# H1DR1x-T.net
KiCad netlist of a schematic drawn in EAGLE
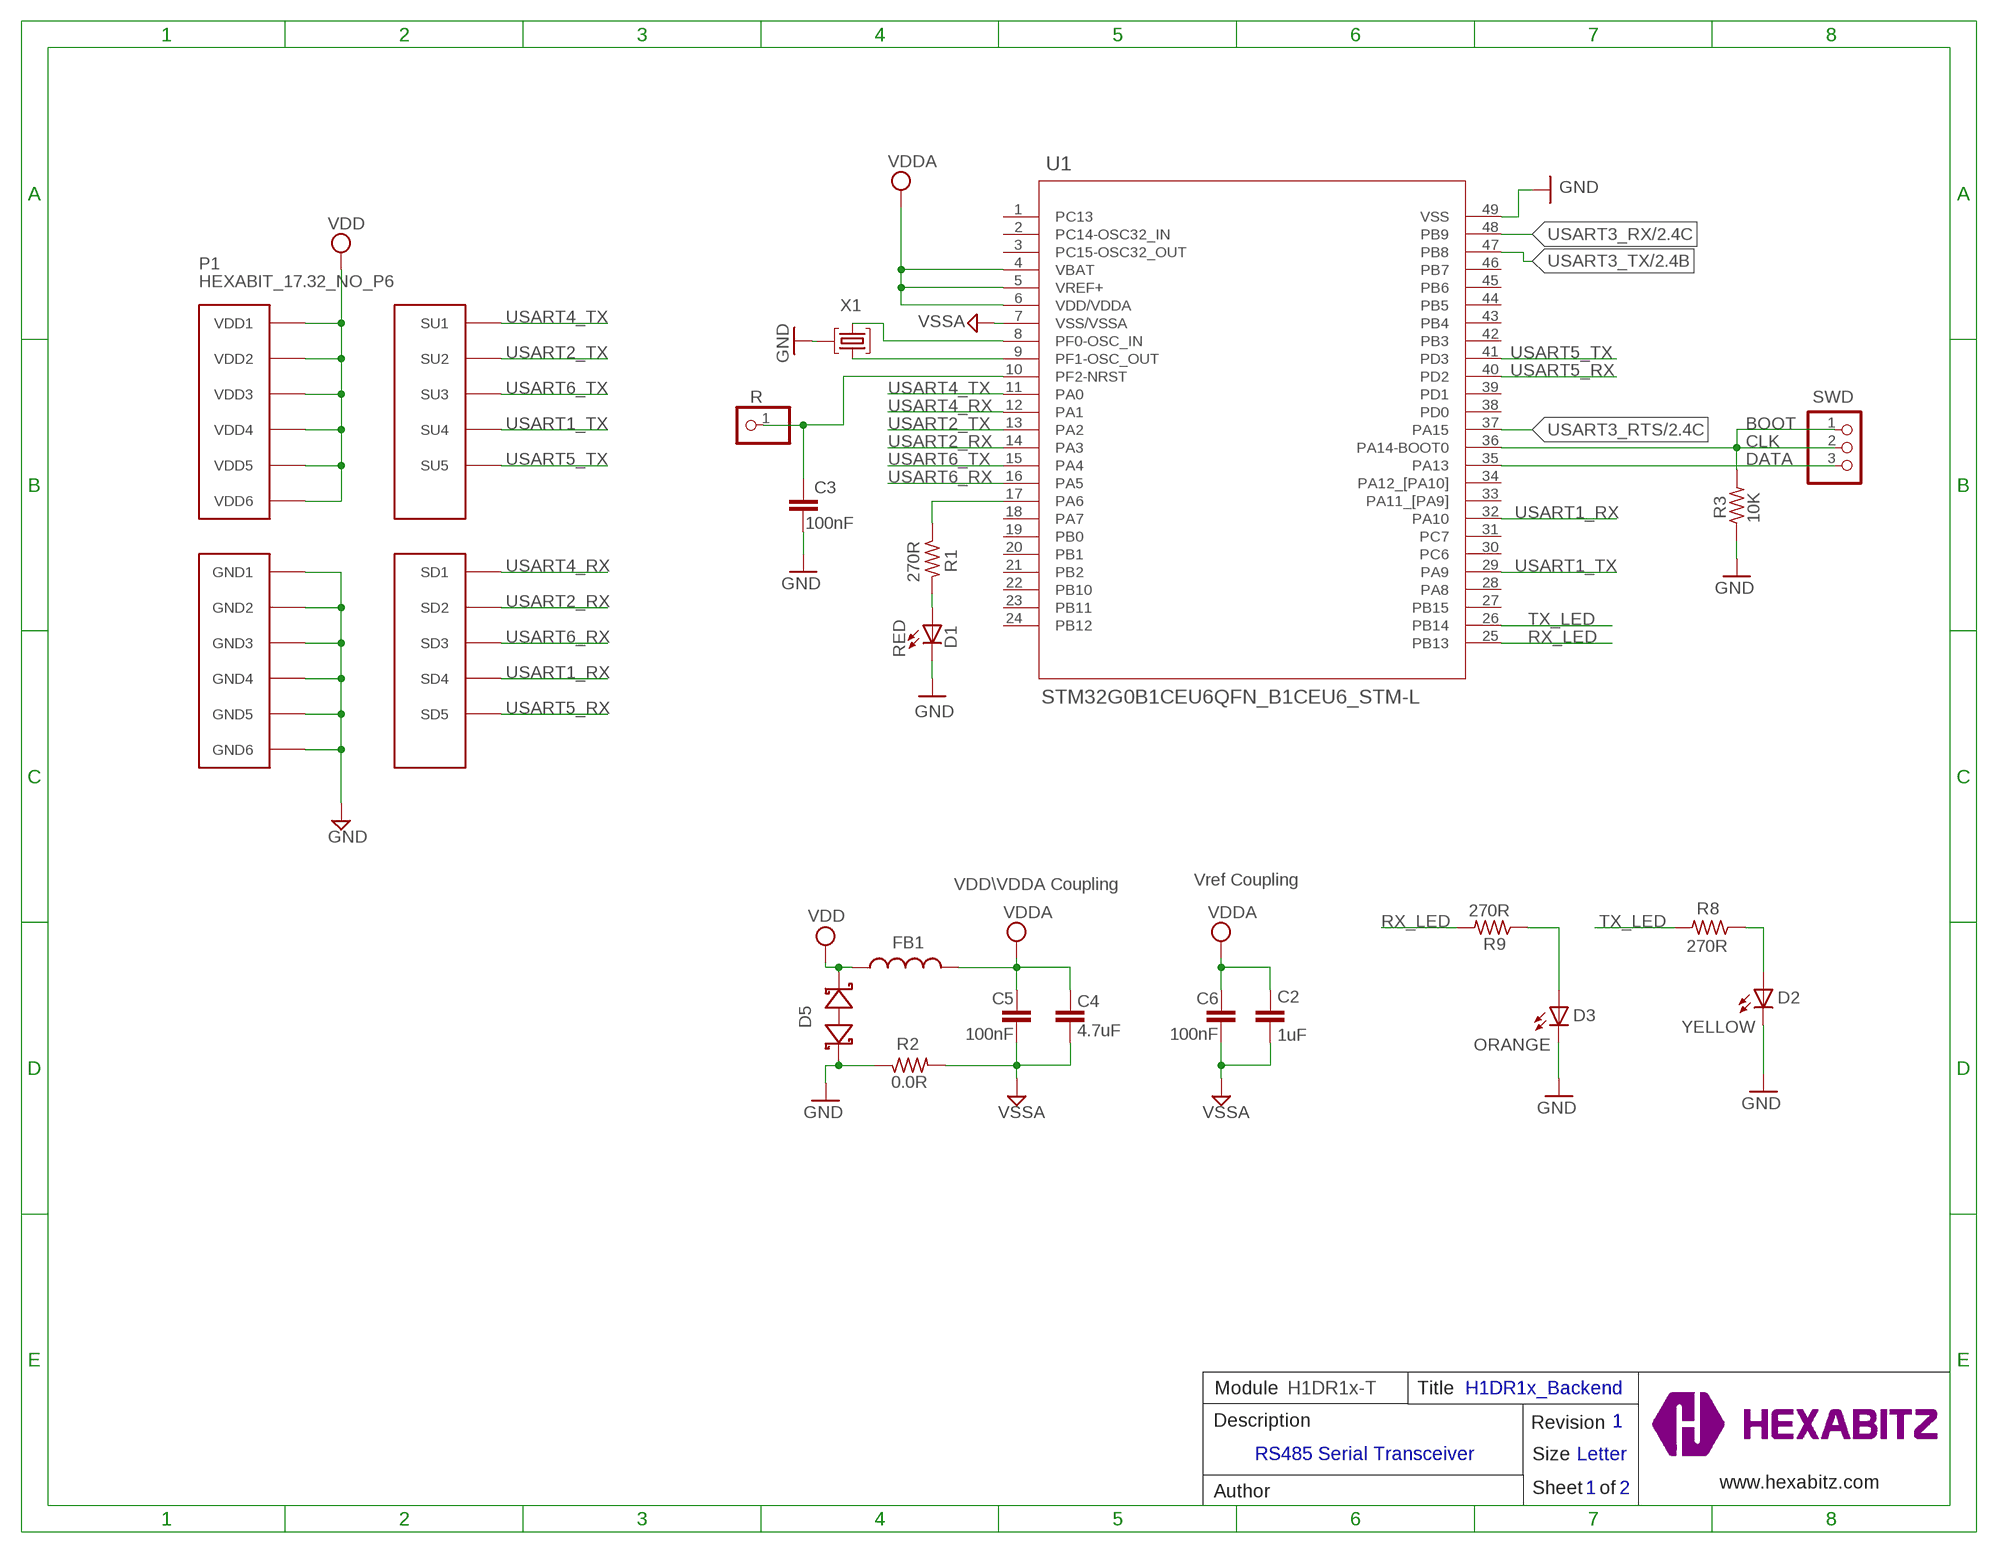
[diagram p0: schematic, sheet 1]
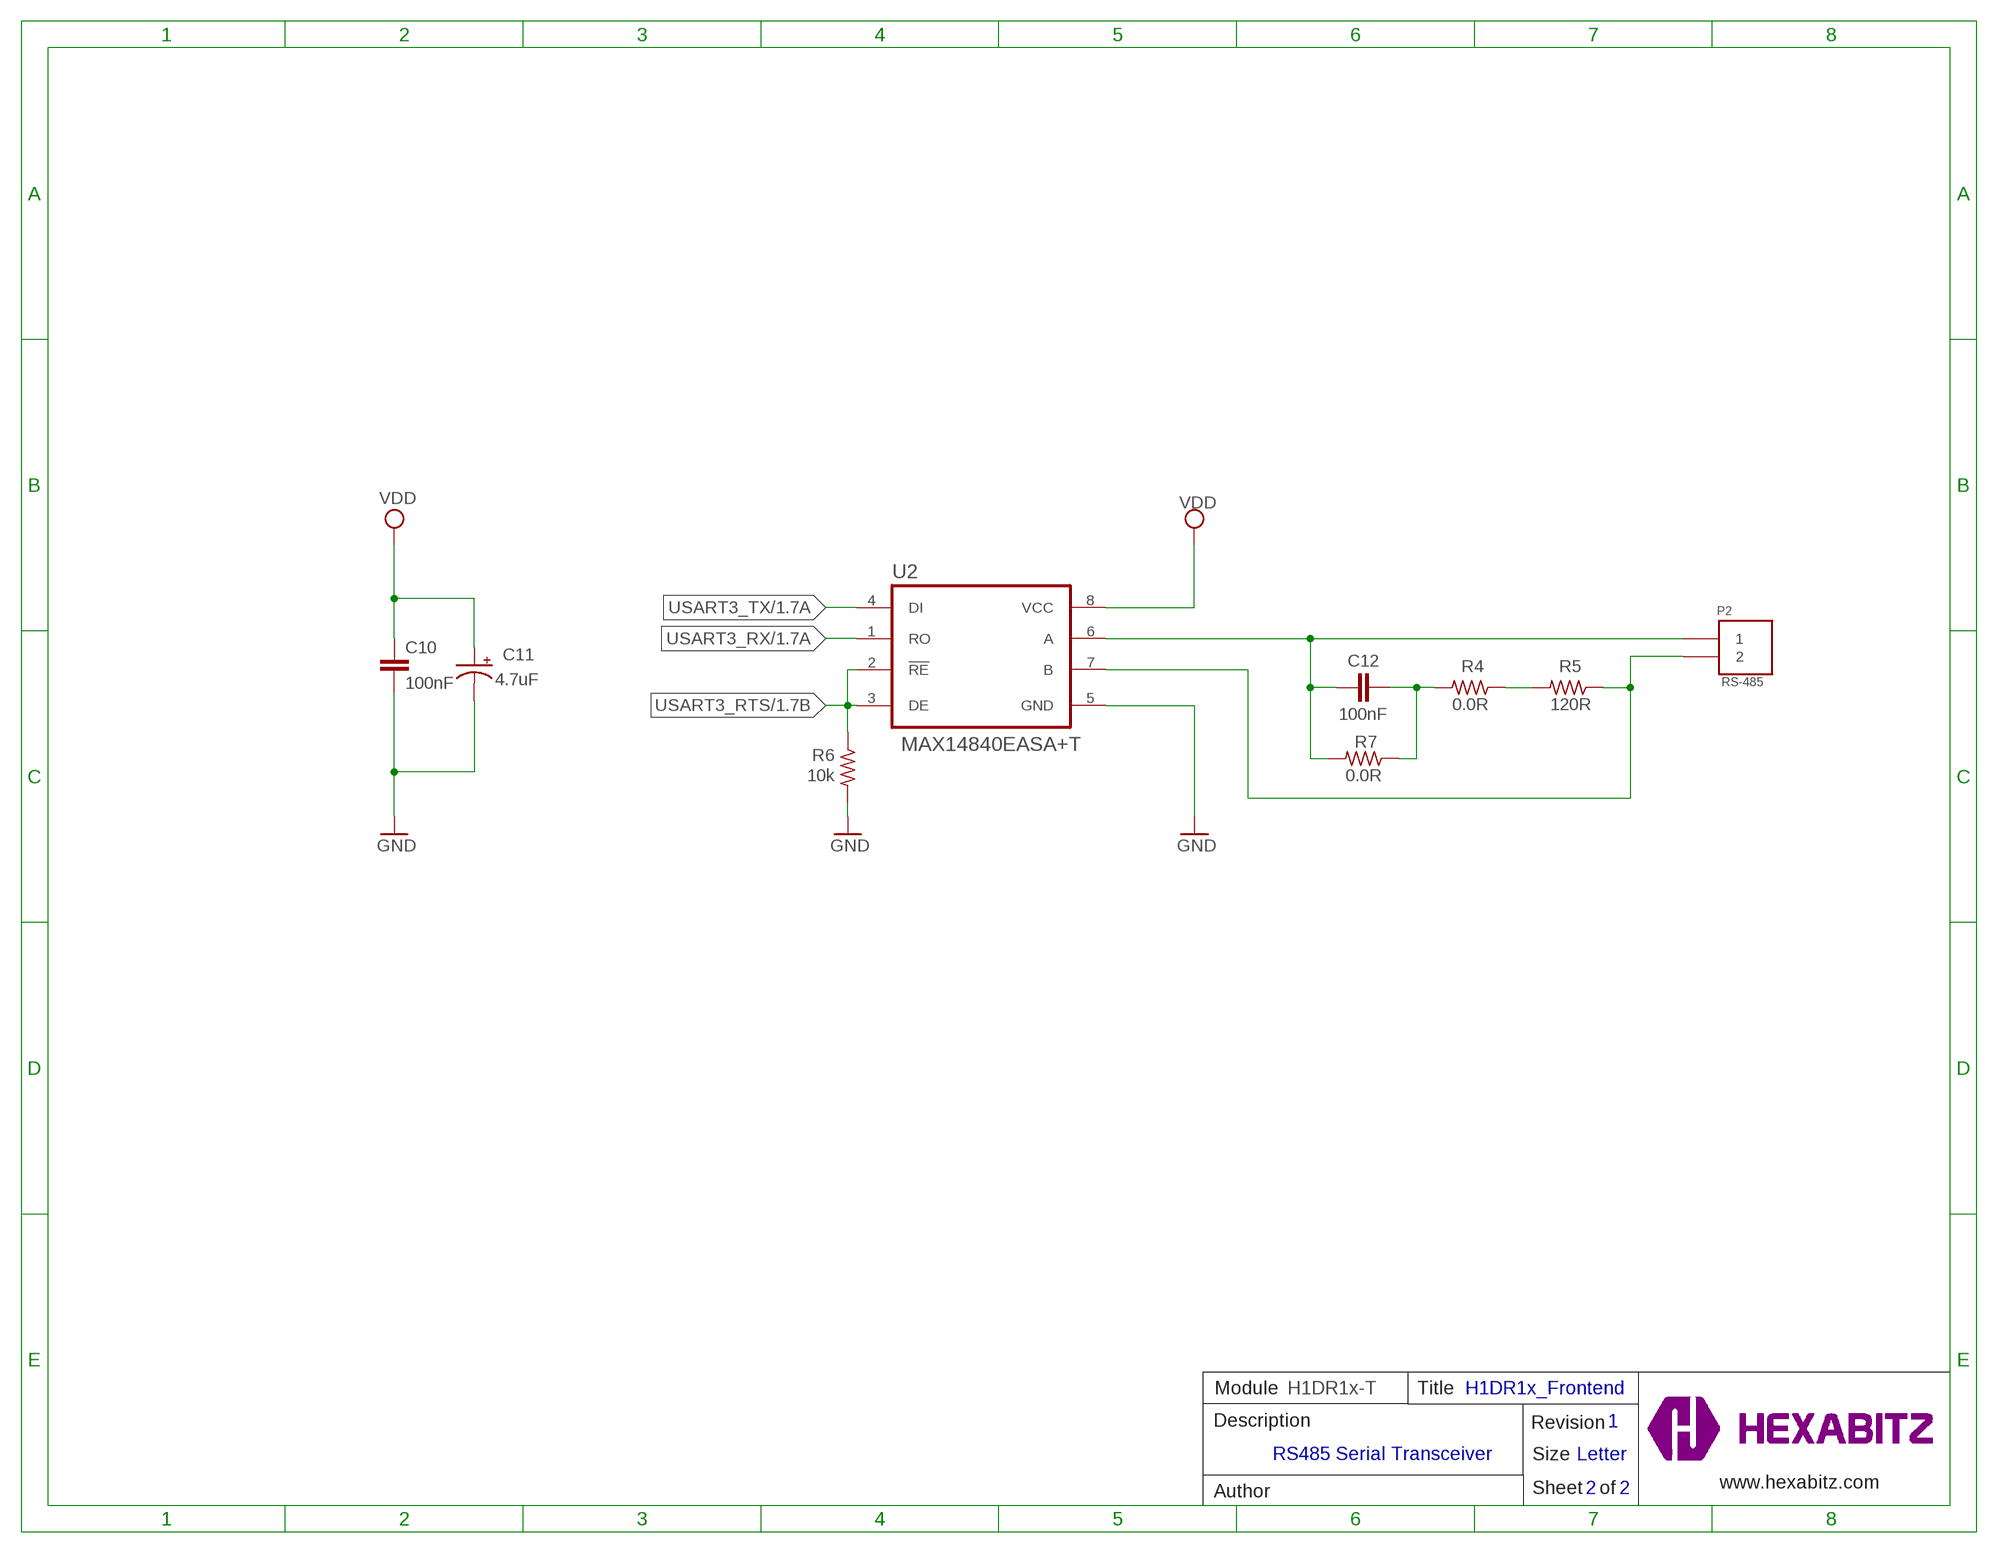
[diagram p1: schematic, sheet 2]

(export (version "E")
  (design (tool "Eeschema 10.0.6"))
  (components
    (comp (ref "C2")
      (value "1uF")
      (footprint "eagle-import:C-0805")
      (libsource (lib "eagle-import") (part "C-0805"))
    )
    (comp (ref "C3")
      (value "100nF")
      (footprint "eagle-import:C-0603")
      (libsource (lib "eagle-import") (part "C-0603"))
    )
    (comp (ref "C4")
      (value "4.7uF")
      (footprint "eagle-import:C-0805")
      (libsource (lib "eagle-import") (part "C-0805"))
    )
    (comp (ref "C5")
      (value "100nF")
      (footprint "eagle-import:C-0603")
      (libsource (lib "eagle-import") (part "C-0603"))
    )
    (comp (ref "C6")
      (value "100nF")
      (footprint "eagle-import:C-0603")
      (libsource (lib "eagle-import") (part "C-0603"))
    )
    (comp (ref "D1")
      (value "RED")
      (footprint "eagle-import:VLMS1300-GS08")
      (fields
        (field (name "MPN") "VLMS1300-GS08")
        (field (name "MFN") "Vishay")
        (field (name "MPN_1") "VLMS1300-GS08")
        (field (name "OCTOPART_URL") "https://octopart.com/vlms1300-gs08-vishay-21709201?r=sp&s=_gcP4_q8T1SC6PJQPTQ9yA")
      )
      (libsource (lib "eagle-import") (part "VLMS1300-GS08"))
    )
    (comp (ref "D2")
      (value "YELLOW")
      (footprint "eagle-import:VLMS1300-GS08")
      (fields
        (field (name "MPN") "VLMS1300-GS08")
        (field (name "OCTOPART_URL") "https://octopart.com/vlms1300-gs08-vishay-21709201?r=sp&s=_gcP4_q8T1SC6PJQPTQ9yA")
      )
      (libsource (lib "eagle-import") (part "VLMS1300-GS08"))
    )
    (comp (ref "D3")
      (value "ORANGE")
      (footprint "eagle-import:VLMS1300-GS08")
      (fields
        (field (name "MPN") "VLMS1300-GS08")
        (field (name "OCTOPART_URL") "https://octopart.com/vlms1300-gs08-vishay-21709201?r=sp&s=_gcP4_q8T1SC6PJQPTQ9yA")
      )
      (libsource (lib "eagle-import") (part "VLMS1300-GS08"))
    )
    (comp (ref "D5")
      (value "BOURNS_CDSOD323-T03SCBOURNS_CDSOD323-T03SC_0_0")
      (footprint "eagle-import:BOURNS_CDSOD323-T03SC_0")
      (fields (field (name "MPN") "CDSOD323-T03SC"))
      (libsource (lib "eagle-import") (part "BOURNS_CDSOD323-T03SCBOURNS_CDSOD323-T03SC_0_0"))
    )
    (comp (ref "FB1")
      (value "FB-TDK_MMZ1608Y300B")
      (footprint "eagle-import:FB-0603")
      (fields
        (field (name "MFN") "TDK ")
        (field (name "MPN") "MMZ1608Y300B")
        (field (name "OCTOPART_URL") "https://octopart.com/mmz1608y300b-tdk-368280?r=sp&s=cd9_2ZEqQ9q9UNBuQgHAiA")
      )
      (libsource (lib "eagle-import") (part "FB-0603"))
    )
    (comp (ref "P1")
      (value "HEXABIT_17.32_NO_P6")
      (footprint "eagle-import:HEXABIT_17.32_NO_P6")
      (libsource (lib "eagle-import") (part "HEXABIT_?_NO_P617.32"))
    )
    (comp (ref "R")
      (value "R")
      (footprint "eagle-import:1X01")
      (fields (field (name "MPN") "87227-1"))
      (libsource (lib "eagle-import") (part "PINHD-1X1"))
    )
    (comp (ref "R1")
      (value "270R")
      (footprint "eagle-import:R-0603")
      (libsource (lib "eagle-import") (part "R-0603"))
    )
    (comp (ref "R2")
      (value "0.0R")
      (footprint "eagle-import:R-0603")
      (fields
        (field (name "MFN") "Yageo")
        (field (name "MPN") "RC0603JR-070RL")
        (field (name "OCTOPART_URL") "https://octopart.com/rc0603jr-070rl-yageo-1241539?r=sp&s=X2NteqRjRNWrnx42Y0aliA")
        (field (name "RESISTANCE") "0.0 Ohm")
      )
      (libsource (lib "eagle-import") (part "R-0603"))
    )
    (comp (ref "R3")
      (value "10K")
      (footprint "eagle-import:R-0603")
      (libsource (lib "eagle-import") (part "R-0603"))
    )
    (comp (ref "R8")
      (value "270R")
      (footprint "eagle-import:R-0603")
      (libsource (lib "eagle-import") (part "R-0603"))
    )
    (comp (ref "R9")
      (value "270R")
      (footprint "eagle-import:R-0603")
      (libsource (lib "eagle-import") (part "R-0603"))
    )
    (comp (ref "SWD")
      (value "PINHD-1X3")
      (footprint "eagle-import:1X03")
      (libsource (lib "eagle-import") (part "PINHD-1X3"))
    )
    (comp (ref "TRIMBLE-LOGO1")
      (value "HEXA-LOGO")
      (footprint "eagle-import:HEXA-LOGO")
      (libsource (lib "eagle-import") (part "HEXA-LOGO"))
    )
    (comp (ref "U1")
      (value "STM32G0B1CEU6QFN_B1CEU6_STM-L")
      (footprint "eagle-import:QFN_B1CEU6_STM-L")
      (fields
        (field (name "MANUFACTURER_PART_NUMBER") "STM32G0B1CEU6")
        (field (name "SPICEPREFIX") "X")
        (field (name "COPYRIGHT") "Copyright (C) 2021 Ultra Librarian. All rights reserved.")
      )
      (libsource (lib "eagle-import") (part "STM32G0B1CEU6QFN_B1CEU6_STM-L"))
    )
    (comp (ref "X1")
      (value "XTALL_CSTCE8M00G52")
      (footprint "eagle-import:XTALL_CSTCE8M00G52")
      (fields (field (name "MPN") "CSTCE8M00G52Z-R0"))
      (libsource (lib "eagle-import") (part "XTALL_CSTCE8M00G52"))
    )
    (comp (ref "C10")
      (value "100nF")
      (footprint "eagle-import:C-0603")
      (fields
        (field (name "CAPACITANCE") "100nF")
        (field (name "MFN") "KEMET")
        (field (name "MPN") "C0603C104K8RACTU")
        (field (name "OCTOPART_URL") "https://octopart.com/c0603c104k8ractu-kemet-145075?r=sp&s=9bS9ASSwSEqMCE9KBEQZ0g")
        (field (name "TOLERANCE") "10%")
        (field (name "VOLTAGE_RATING") "10V")
      )
      (libsource (lib "eagle-import") (part "C-0603"))
    )
    (comp (ref "C11")
      (value "4.7uF")
      (footprint "eagle-import:C-0805-POL")
      (fields
        (field (name "CAPACITANCE") "4.7uF")
        (field (name "MFN") "Murata")
        (field (name "MPN") "GRM21BC81E475KA12L")
        (field (name "OCTOPART_URL") "https://octopart.com/grm21bc81e475ka12l-murata-10331911?r=sp&s=RY3qZSD8T6mG6TC9CHI5qQ")
        (field (name "TOLERANCE") "10%")
        (field (name "VOLTAGE_RATING") "25V")
      )
      (libsource (lib "eagle-import") (part "C-0805-POL"))
    )
    (comp (ref "C12")
      (value "100nF")
      (footprint "eagle-import:C-0603")
      (fields
        (field (name "CAPACITANCE") "100nF")
        (field (name "MFN") "AVX")
        (field (name "MPN") "0603YC104K4T2A")
        (field (name "OCTOPART_URL") "https://octopart.com/0603yc104k4t2a-avx+interconnect+%2F+elco-8120651")
        (field (name "TOLERANCE") "10%")
        (field (name "VOLTAGE_RATING") "16V")
      )
      (libsource (lib "eagle-import") (part "C-0603"))
    )
    (comp (ref "P2")
      (value "RS-485")
      (footprint "eagle-import:1546111-2")
      (fields (field (name "MPN") "1546111-2"))
      (libsource (lib "eagle-import") (part "1546111-2"))
    )
    (comp (ref "R4")
      (value "0.0R")
      (footprint "eagle-import:R-0603")
      (fields
        (field (name "MFN") "Vishay")
        (field (name "MPN") "CRCW06030000Z0EA")
        (field (name "OCTOPART_URL") "https://octopart.com/crcw06030000z0ea-vishay-39556096#")
        (field (name "RESISTANCE") "0.0 Ohm")
      )
      (libsource (lib "eagle-import") (part "R-0603"))
    )
    (comp (ref "R5")
      (value "120R")
      (footprint "eagle-import:R-0603")
      (fields
        (field (name "MFN") "Panasonic")
        (field (name "MPN") "ERJP6WF1200V")
        (field (name "OCTOPART_URL") "https://octopart.com/erjp6wf1200v-panasonic-25949195?r=sp#")
        (field (name "RESISTANCE") "120R")
        (field (name "TOLERANCE") "1%")
      )
      (libsource (lib "eagle-import") (part "R-0603"))
    )
    (comp (ref "R6")
      (value "10k")
      (footprint "eagle-import:R-0603")
      (fields
        (field (name "MFN") "Vishay")
        (field (name "MPN") "CRCW060310K0JNEB")
        (field (name "OCTOPART_URL") "https://octopart.com/crcw060310k0jneb-vishay+dale-46603268")
        (field (name "RESISTANCE") "10k")
        (field (name "TOLERANCE") "5%")
      )
      (libsource (lib "eagle-import") (part "R-0603"))
    )
    (comp (ref "R7")
      (value "0.0R")
      (footprint "eagle-import:R-0603")
      (fields
        (field (name "MFN") "Vishay")
        (field (name "MPN") "CRCW06030000Z0EA")
        (field (name "OCTOPART_URL") "https://octopart.com/crcw06030000z0ea-vishay-39556096#")
        (field (name "RESISTANCE") "0.0 Ohm")
      )
      (libsource (lib "eagle-import") (part "R-0603"))
    )
    (comp (ref "U2")
      (value "MAX14840EASA+T")
      (footprint "eagle-import:SOIC127P600X175-8N")
      (fields (field (name "MF") "Analog Devices"))
      (libsource (lib "eagle-import") (part "MAX14840EASA+T"))
    )
  )
  (nets
    (net (code "1") (name "CLK") (class "Default")
      (node (ref "R3") (pin "2") (pinfunction "2_2") (pintype "passive"))
      (node (ref "SWD") (pin "1") (pinfunction "1_1") (pintype "passive"))
      (node (ref "SWD") (pin "2") (pinfunction "2_2") (pintype "passive"))
      (node (ref "U1") (pin "36") (pinfunction "PA14-BOOT0_36") (pintype "bidirectional"))
    )
    (net (code "2") (name "DATA") (class "Default")
      (node (ref "SWD") (pin "3") (pinfunction "3_3") (pintype "passive"))
      (node (ref "U1") (pin "35") (pinfunction "PA13_35") (pintype "bidirectional"))
    )
    (net (code "3") (name "GND") (class "Default")
      (node (ref "C10") (pin "2") (pinfunction "2_2") (pintype "passive"))
      (node (ref "C11") (pin "2") (pinfunction "-_2") (pintype "passive"))
      (node (ref "C3") (pin "2") (pinfunction "2_2") (pintype "passive"))
      (node (ref "D1") (pin "C") (pinfunction "C_C") (pintype "passive"))
      (node (ref "D2") (pin "C") (pinfunction "C_C") (pintype "passive"))
      (node (ref "D3") (pin "C") (pinfunction "C_C") (pintype "passive"))
      (node (ref "D5") (pin "1") (pinfunction "A_1") (pintype "passive"))
      (node (ref "P1") (pin "PAD_PD10") (pinfunction "GND4_PAD_PD10") (pintype "power_in"))
      (node (ref "P1") (pin "PAD_PD11") (pinfunction "GND5_PAD_PD11") (pintype "power_in"))
      (node (ref "P1") (pin "PAD_PD12") (pinfunction "GND6_PAD_PD12") (pintype "power_in"))
      (node (ref "P1") (pin "PAD_PD7") (pinfunction "GND1_PAD_PD7") (pintype "power_in"))
      (node (ref "P1") (pin "PAD_PD8") (pinfunction "GND2_PAD_PD8") (pintype "power_in"))
      (node (ref "P1") (pin "PAD_PD9") (pinfunction "GND3_PAD_PD9") (pintype "power_in"))
      (node (ref "R2") (pin "1") (pinfunction "1_1") (pintype "passive"))
      (node (ref "R3") (pin "1") (pinfunction "1_1") (pintype "passive"))
      (node (ref "R6") (pin "2") (pinfunction "2_2") (pintype "passive"))
      (node (ref "U1") (pin "49") (pinfunction "VSS_49") (pintype "passive"))
      (node (ref "U2") (pin "5") (pinfunction "GND_5") (pintype "power_in"))
      (node (ref "X1") (pin "P$2") (pinfunction "2_P$2") (pintype "passive"))
    )
    (net (code "4") (name "Net-(C12-Pad2)") (class "Default")
      (node (ref "C12") (pin "2") (pinfunction "2_2") (pintype "passive"))
      (node (ref "R4") (pin "2") (pinfunction "2_2") (pintype "passive"))
      (node (ref "R7") (pin "1") (pinfunction "1_1") (pintype "passive"))
    )
    (net (code "5") (name "Net-(D1-PadA)") (class "Default")
      (node (ref "D1") (pin "A") (pinfunction "A_A") (pintype "passive"))
      (node (ref "R1") (pin "2") (pinfunction "2_2") (pintype "passive"))
    )
    (net (code "6") (name "Net-(D2-PadA)") (class "Default")
      (node (ref "D2") (pin "A") (pinfunction "A_A") (pintype "passive"))
      (node (ref "R8") (pin "1") (pinfunction "1_1") (pintype "passive"))
    )
    (net (code "7") (name "Net-(D3-PadA)") (class "Default")
      (node (ref "D3") (pin "A") (pinfunction "A_A") (pintype "passive"))
      (node (ref "R9") (pin "1") (pinfunction "1_1") (pintype "passive"))
    )
    (net (code "8") (name "Net-(R4-Pad1)") (class "Default")
      (node (ref "R4") (pin "1") (pinfunction "1_1") (pintype "passive"))
      (node (ref "R5") (pin "2") (pinfunction "2_2") (pintype "passive"))
    )
    (net (code "9") (name "Net-(U1-PA6)") (class "Default")
      (node (ref "R1") (pin "1") (pinfunction "1_1") (pintype "passive"))
      (node (ref "U1") (pin "17") (pinfunction "PA6_17") (pintype "bidirectional"))
    )
    (net (code "10") (name "Net-(U1-PF0-OSC_IN)") (class "Default")
      (node (ref "U1") (pin "8") (pinfunction "PF0-OSC_IN_8") (pintype "bidirectional"))
      (node (ref "X1") (pin "P$3") (pinfunction "3_P$3") (pintype "passive"))
    )
    (net (code "11") (name "Net-(U1-PF1-OSC_OUT)") (class "Default")
      (node (ref "U1") (pin "9") (pinfunction "PF1-OSC_OUT_9") (pintype "output"))
      (node (ref "X1") (pin "P$1") (pinfunction "1_P$1") (pintype "passive"))
    )
    (net (code "12") (name "Net-(U1-PF2-NRST)") (class "Default")
      (node (ref "C3") (pin "1") (pinfunction "1_1") (pintype "passive"))
      (node (ref "R") (pin "1") (pinfunction "1_1") (pintype "passive"))
      (node (ref "U1") (pin "10") (pinfunction "PF2-NRST_10") (pintype "bidirectional"))
    )
    (net (code "13") (name "Net-(U2-A)") (class "Default")
      (node (ref "C12") (pin "1") (pinfunction "1_1") (pintype "passive"))
      (node (ref "P2") (pin "1") (pinfunction "1_1") (pintype "power_in"))
      (node (ref "R7") (pin "2") (pinfunction "2_2") (pintype "passive"))
      (node (ref "U2") (pin "6") (pinfunction "A_6") (pintype "bidirectional"))
    )
    (net (code "14") (name "Net-(U2-B)") (class "Default")
      (node (ref "P2") (pin "2") (pinfunction "2_2") (pintype "power_in"))
      (node (ref "R5") (pin "1") (pinfunction "1_1") (pintype "passive"))
      (node (ref "U2") (pin "7") (pinfunction "B_7") (pintype "bidirectional"))
    )
    (net (code "15") (name "RX_LED") (class "Default")
      (node (ref "R9") (pin "2") (pinfunction "2_2") (pintype "passive"))
      (node (ref "U1") (pin "25") (pinfunction "PB13_25") (pintype "bidirectional"))
    )
    (net (code "16") (name "TX_LED") (class "Default")
      (node (ref "R8") (pin "2") (pinfunction "2_2") (pintype "passive"))
      (node (ref "U1") (pin "26") (pinfunction "PB14_26") (pintype "bidirectional"))
    )
    (net (code "17") (name "USART1_RX") (class "Default")
      (node (ref "P1") (pin "PAD_PD4") (pinfunction "SD4_PAD_PD4") (pintype "bidirectional"))
      (node (ref "U1") (pin "32") (pinfunction "PA10_32") (pintype "bidirectional"))
    )
    (net (code "18") (name "USART1_TX") (class "Default")
      (node (ref "P1") (pin "PAD_PU4") (pinfunction "SU4_PAD_PU4") (pintype "bidirectional"))
      (node (ref "U1") (pin "29") (pinfunction "PA9_29") (pintype "bidirectional"))
    )
    (net (code "19") (name "USART2_RX") (class "Default")
      (node (ref "P1") (pin "PAD_PD2") (pinfunction "SD2_PAD_PD2") (pintype "bidirectional"))
      (node (ref "U1") (pin "14") (pinfunction "PA3_14") (pintype "bidirectional"))
    )
    (net (code "20") (name "USART2_TX") (class "Default")
      (node (ref "P1") (pin "PAD_PU2") (pinfunction "SU2_PAD_PU2") (pintype "bidirectional"))
      (node (ref "U1") (pin "13") (pinfunction "PA2_13") (pintype "bidirectional"))
    )
    (net (code "21") (name "USART3_RTS") (class "Default")
      (node (ref "R6") (pin "1") (pinfunction "1_1") (pintype "passive"))
      (node (ref "U1") (pin "37") (pinfunction "PA15_37") (pintype "bidirectional"))
      (node (ref "U2") (pin "2") (pinfunction "~{RE}_2") (pintype "bidirectional"))
      (node (ref "U2") (pin "3") (pinfunction "DE_3") (pintype "bidirectional"))
    )
    (net (code "22") (name "USART3_RX") (class "Default")
      (node (ref "U1") (pin "48") (pinfunction "PB9_48") (pintype "bidirectional"))
      (node (ref "U2") (pin "1") (pinfunction "RO_1") (pintype "bidirectional"))
    )
    (net (code "23") (name "USART3_TX") (class "Default")
      (node (ref "U1") (pin "47") (pinfunction "PB8_47") (pintype "bidirectional"))
      (node (ref "U2") (pin "4") (pinfunction "DI_4") (pintype "input"))
    )
    (net (code "24") (name "USART4_RX") (class "Default")
      (node (ref "P1") (pin "PAD_PD1") (pinfunction "SD1_PAD_PD1") (pintype "bidirectional"))
      (node (ref "U1") (pin "12") (pinfunction "PA1_12") (pintype "bidirectional"))
    )
    (net (code "25") (name "USART4_TX") (class "Default")
      (node (ref "P1") (pin "PAD_PU1") (pinfunction "SU1_PAD_PU1") (pintype "bidirectional"))
      (node (ref "U1") (pin "11") (pinfunction "PA0_11") (pintype "bidirectional"))
    )
    (net (code "26") (name "USART5_RX") (class "Default")
      (node (ref "P1") (pin "PAD_PD5") (pinfunction "SD5_PAD_PD5") (pintype "bidirectional"))
      (node (ref "U1") (pin "40") (pinfunction "PD2_40") (pintype "bidirectional"))
    )
    (net (code "27") (name "USART5_TX") (class "Default")
      (node (ref "P1") (pin "PAD_PU5") (pinfunction "SU5_PAD_PU5") (pintype "bidirectional"))
      (node (ref "U1") (pin "41") (pinfunction "PD3_41") (pintype "bidirectional"))
    )
    (net (code "28") (name "USART6_RX") (class "Default")
      (node (ref "P1") (pin "PAD_PD3") (pinfunction "SD3_PAD_PD3") (pintype "bidirectional"))
      (node (ref "U1") (pin "16") (pinfunction "PA5_16") (pintype "bidirectional"))
    )
    (net (code "29") (name "USART6_TX") (class "Default")
      (node (ref "P1") (pin "PAD_PU3") (pinfunction "SU3_PAD_PU3") (pintype "bidirectional"))
      (node (ref "U1") (pin "15") (pinfunction "PA4_15") (pintype "bidirectional"))
    )
    (net (code "30") (name "VDD") (class "Default")
      (node (ref "C10") (pin "1") (pinfunction "1_1") (pintype "passive"))
      (node (ref "C11") (pin "1") (pinfunction "+_1") (pintype "passive"))
      (node (ref "D5") (pin "2") (pinfunction "C_2") (pintype "passive"))
      (node (ref "FB1") (pin "2") (pinfunction "2_2") (pintype "passive"))
      (node (ref "P1") (pin "PAD_PU10") (pinfunction "VDD4_PAD_PU10") (pintype "power_in"))
      (node (ref "P1") (pin "PAD_PU11") (pinfunction "VDD5_PAD_PU11") (pintype "power_in"))
      (node (ref "P1") (pin "PAD_PU12") (pinfunction "VDD6_PAD_PU12") (pintype "power_in"))
      (node (ref "P1") (pin "PAD_PU7") (pinfunction "VDD1_PAD_PU7") (pintype "power_in"))
      (node (ref "P1") (pin "PAD_PU8") (pinfunction "VDD2_PAD_PU8") (pintype "power_in"))
      (node (ref "P1") (pin "PAD_PU9") (pinfunction "VDD3_PAD_PU9") (pintype "power_in"))
      (node (ref "U2") (pin "8") (pinfunction "VCC_8") (pintype "power_in"))
    )
    (net (code "31") (name "VDDA") (class "Default")
      (node (ref "C2") (pin "1") (pinfunction "1_1") (pintype "passive"))
      (node (ref "C4") (pin "1") (pinfunction "1_1") (pintype "passive"))
      (node (ref "C5") (pin "1") (pinfunction "1_1") (pintype "passive"))
      (node (ref "C6") (pin "1") (pinfunction "1_1") (pintype "passive"))
      (node (ref "FB1") (pin "1") (pinfunction "1_1") (pintype "passive"))
      (node (ref "U1") (pin "4") (pinfunction "VBAT_4") (pintype "passive"))
      (node (ref "U1") (pin "5") (pinfunction "VREF+_5") (pintype "power_in"))
      (node (ref "U1") (pin "6") (pinfunction "VDD/VDDA_6") (pintype "power_in"))
    )
    (net (code "32") (name "VSSA") (class "Default")
      (node (ref "C2") (pin "2") (pinfunction "2_2") (pintype "passive"))
      (node (ref "C4") (pin "2") (pinfunction "2_2") (pintype "passive"))
      (node (ref "C5") (pin "2") (pinfunction "2_2") (pintype "passive"))
      (node (ref "C6") (pin "2") (pinfunction "2_2") (pintype "passive"))
      (node (ref "R2") (pin "2") (pinfunction "2_2") (pintype "passive"))
      (node (ref "U1") (pin "7") (pinfunction "VSS/VSSA_7") (pintype "passive"))
    )
    (net (code "33") (name "unconnected-(U1-PA7-Pad18)") (class "Default")
      (node (ref "U1") (pin "18") (pinfunction "PA7_18") (pintype "bidirectional"))
    )
    (net (code "34") (name "unconnected-(U1-PA8-Pad28)") (class "Default")
      (node (ref "U1") (pin "28") (pinfunction "PA8_28") (pintype "bidirectional"))
    )
    (net (code "35") (name "unconnected-(U1-PA11_[PA9]-Pad33)") (class "Default")
      (node (ref "U1") (pin "33") (pinfunction "PA11_[PA9]_33") (pintype "bidirectional"))
    )
    (net (code "36") (name "unconnected-(U1-PA12_[PA10]-Pad34)") (class "Default")
      (node (ref "U1") (pin "34") (pinfunction "PA12_[PA10]_34") (pintype "bidirectional"))
    )
    (net (code "37") (name "unconnected-(U1-PB0-Pad19)") (class "Default")
      (node (ref "U1") (pin "19") (pinfunction "PB0_19") (pintype "bidirectional"))
    )
    (net (code "38") (name "unconnected-(U1-PB1-Pad20)") (class "Default")
      (node (ref "U1") (pin "20") (pinfunction "PB1_20") (pintype "bidirectional"))
    )
    (net (code "39") (name "unconnected-(U1-PB2-Pad21)") (class "Default")
      (node (ref "U1") (pin "21") (pinfunction "PB2_21") (pintype "bidirectional"))
    )
    (net (code "40") (name "unconnected-(U1-PB3-Pad42)") (class "Default")
      (node (ref "U1") (pin "42") (pinfunction "PB3_42") (pintype "bidirectional"))
    )
    (net (code "41") (name "unconnected-(U1-PB4-Pad43)") (class "Default")
      (node (ref "U1") (pin "43") (pinfunction "PB4_43") (pintype "bidirectional"))
    )
    (net (code "42") (name "unconnected-(U1-PB5-Pad44)") (class "Default")
      (node (ref "U1") (pin "44") (pinfunction "PB5_44") (pintype "bidirectional"))
    )
    (net (code "43") (name "unconnected-(U1-PB6-Pad45)") (class "Default")
      (node (ref "U1") (pin "45") (pinfunction "PB6_45") (pintype "bidirectional"))
    )
    (net (code "44") (name "unconnected-(U1-PB7-Pad46)") (class "Default")
      (node (ref "U1") (pin "46") (pinfunction "PB7_46") (pintype "bidirectional"))
    )
    (net (code "45") (name "unconnected-(U1-PB10-Pad22)") (class "Default")
      (node (ref "U1") (pin "22") (pinfunction "PB10_22") (pintype "bidirectional"))
    )
    (net (code "46") (name "unconnected-(U1-PB11-Pad23)") (class "Default")
      (node (ref "U1") (pin "23") (pinfunction "PB11_23") (pintype "bidirectional"))
    )
    (net (code "47") (name "unconnected-(U1-PB12-Pad24)") (class "Default")
      (node (ref "U1") (pin "24") (pinfunction "PB12_24") (pintype "bidirectional"))
    )
    (net (code "48") (name "unconnected-(U1-PB15-Pad27)") (class "Default")
      (node (ref "U1") (pin "27") (pinfunction "PB15_27") (pintype "bidirectional"))
    )
    (net (code "49") (name "unconnected-(U1-PC6-Pad30)") (class "Default")
      (node (ref "U1") (pin "30") (pinfunction "PC6_30") (pintype "bidirectional"))
    )
    (net (code "50") (name "unconnected-(U1-PC7-Pad31)") (class "Default")
      (node (ref "U1") (pin "31") (pinfunction "PC7_31") (pintype "bidirectional"))
    )
    (net (code "51") (name "unconnected-(U1-PC13-Pad1)") (class "Default")
      (node (ref "U1") (pin "1") (pinfunction "PC13_1") (pintype "bidirectional"))
    )
    (net (code "52") (name "unconnected-(U1-PC14-OSC32_IN-Pad2)") (class "Default")
      (node (ref "U1") (pin "2") (pinfunction "PC14-OSC32_IN_2") (pintype "bidirectional"))
    )
    (net (code "53") (name "unconnected-(U1-PC15-OSC32_OUT-Pad3)") (class "Default")
      (node (ref "U1") (pin "3") (pinfunction "PC15-OSC32_OUT_3") (pintype "output"))
    )
    (net (code "54") (name "unconnected-(U1-PD0-Pad38)") (class "Default")
      (node (ref "U1") (pin "38") (pinfunction "PD0_38") (pintype "bidirectional"))
    )
    (net (code "55") (name "unconnected-(U1-PD1-Pad39)") (class "Default")
      (node (ref "U1") (pin "39") (pinfunction "PD1_39") (pintype "bidirectional"))
    )
  )
)
